# JACart.net
KiCad netlist of a schematic drawn in EAGLE
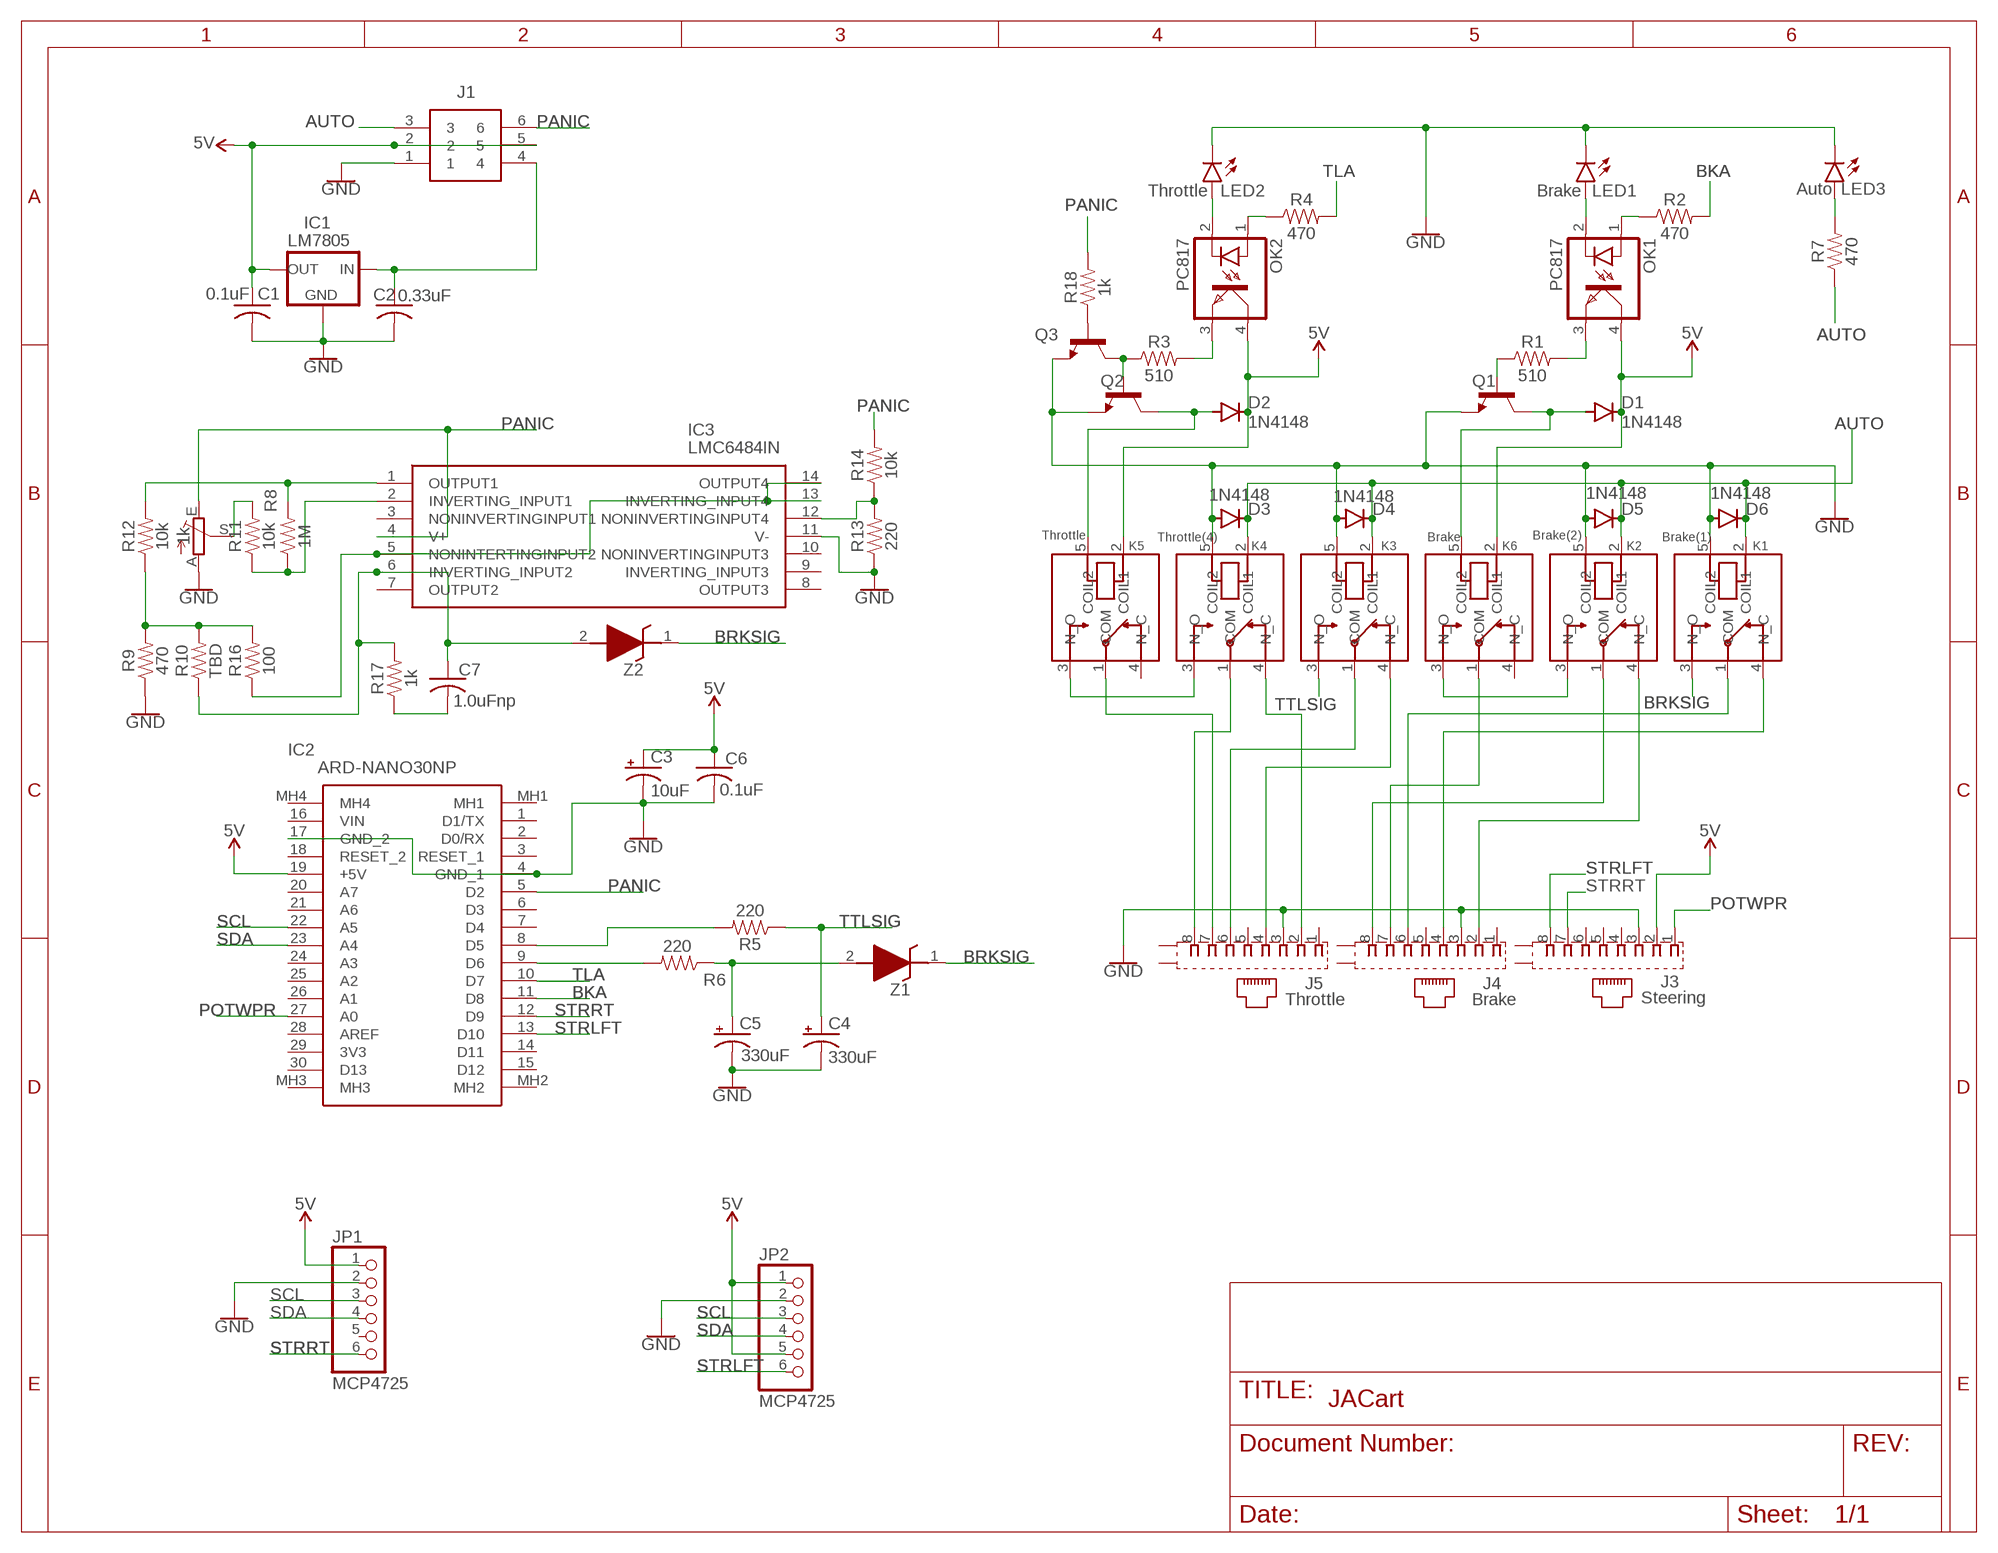
[diagram p0: schematic, sheet 1]

(export (version "E")
  (design (tool "Eeschema 10.0.6"))
  (components
    (comp (ref "C1")
      (value "0.1uF")
      (footprint "eagle-import:C050-024X044")
      (fields (field (name "C1") "0.1uF"))
      (libsource (lib "eagle-import") (part "adafruit_C-US050-024X044"))
    )
    (comp (ref "C2")
      (value "0.33uF")
      (footprint "eagle-import:C050-024X044")
      (fields (field (name "C2") "0.33uF"))
      (libsource (lib "eagle-import") (part "adafruit_C-US050-024X044"))
    )
    (comp (ref "C3")
      (value "10uF")
      (footprint "eagle-import:CPOL-RADIAL-2.5MM-5MM")
      (libsource (lib "eagle-import") (part "10UF-POLAR-RADIAL-2.5MM-25V-20%"))
    )
    (comp (ref "C4")
      (value "330uF")
      (footprint "eagle-import:PANASONIC_A")
      (libsource (lib "eagle-import") (part "330UF-PA"))
    )
    (comp (ref "C5")
      (value "330uF")
      (footprint "eagle-import:PANASONIC_A")
      (libsource (lib "eagle-import") (part "330UF-PA"))
    )
    (comp (ref "C6")
      (value "0.1uF")
      (footprint "eagle-import:C050-024X044")
      (fields (field (name "C6") "0.1uF"))
      (libsource (lib "eagle-import") (part "adafruit_C-US050-024X044"))
    )
    (comp (ref "C7")
      (value "1.0uF")
      (footprint "eagle-import:C050-024X044")
      (fields (field (name "C7") "1.0uFnp"))
      (libsource (lib "eagle-import") (part "C-US050-024X044"))
    )
    (comp (ref "D1")
      (value "1N4148")
      (footprint "eagle-import:DO35-7")
      (libsource (lib "eagle-import") (part "1N4148DO35-7"))
    )
    (comp (ref "D2")
      (value "1N4148")
      (footprint "eagle-import:DO35-7")
      (libsource (lib "eagle-import") (part "1N4148DO35-7"))
    )
    (comp (ref "D3")
      (value "1N4148")
      (footprint "eagle-import:DO35-7")
      (libsource (lib "eagle-import") (part "1N4148DO35-7"))
    )
    (comp (ref "D4")
      (value "1N4148")
      (footprint "eagle-import:DO35-7")
      (libsource (lib "eagle-import") (part "1N4148DO35-7"))
    )
    (comp (ref "D5")
      (value "1N4148")
      (footprint "eagle-import:DO35-7")
      (libsource (lib "eagle-import") (part "1N4148DO35-7"))
    )
    (comp (ref "D6")
      (value "1N4148")
      (footprint "eagle-import:DO35-7")
      (libsource (lib "eagle-import") (part "1N4148DO35-7"))
    )
    (comp (ref "IC1")
      (value "LM7805")
      (footprint "eagle-import:78XXS")
      (libsource (lib "eagle-import") (part "7805-VR"))
    )
    (comp (ref "IC2")
      (value "ARD-NANO30NP")
      (footprint "eagle-import:ARDNANO30NP")
      (fields (field (name "MOUSER_PART_NUMBER") "992-ARD-NANO30NP"))
      (libsource (lib "eagle-import") (part "ARD-NANO30NP"))
    )
    (comp (ref "IC3")
      (value "LMC6484IN")
      (footprint "eagle-import:DIP794W56P254L1905H533Q14N")
      (fields (field (name "MOUSER_PART_NUMBER") "926-LMC6484IN"))
      (libsource (lib "eagle-import") (part "LMC6484IN"))
    )
    (comp (ref "J1")
      (value "39-30-1060")
      (footprint "eagle-import:39-30-1060_1")
      (fields (field (name "MOUSER_PART_NUMBER") "538-39-30-1060"))
      (libsource (lib "eagle-import") (part "39-30-1060"))
    )
    (comp (ref "J3")
      (value "Steering")
      (footprint "eagle-import:GLX-S-88M")
      (libsource (lib "eagle-import") (part "RJ45-RTANGL"))
    )
    (comp (ref "J4")
      (value "Brake")
      (footprint "eagle-import:GLX-S-88M")
      (fields (field (name "MF") "J4"))
      (libsource (lib "eagle-import") (part "RJ45-RTANGL"))
    )
    (comp (ref "J5")
      (value "Throttle")
      (footprint "eagle-import:GLX-S-88M")
      (libsource (lib "eagle-import") (part "RJ45-RTANGL"))
    )
    (comp (ref "JP1")
      (value "MCP4725")
      (footprint "eagle-import:1X06_ROUND_70")
      (libsource (lib "eagle-import") (part "HEADER-1X670MIL"))
    )
    (comp (ref "JP2")
      (value "MCP4725")
      (footprint "eagle-import:1X06_ROUND_70")
      (libsource (lib "eagle-import") (part "HEADER-1X670MIL"))
    )
    (comp (ref "K1")
      (value "Brake(1)")
      (footprint "eagle-import:RELAY_JS1-5V-F")
      (fields (field (name "MF") "Panasonic Electric") (field (name "MP") "JS1-5V-F"))
      (libsource (lib "eagle-import") (part "RELAY-SPDT"))
    )
    (comp (ref "K2")
      (value "Brake(2)")
      (footprint "eagle-import:RELAY_JS1-5V-F")
      (fields (field (name "MF") "Panasonic Electric") (field (name "MP") "JS1-5V-F"))
      (libsource (lib "eagle-import") (part "RELAY-SPDT"))
    )
    (comp (ref "K3")
      (value "Throttle(3)")
      (footprint "eagle-import:RELAY_JS1-5V-F")
      (fields (field (name "MF") "Panasonic Electric") (field (name "MP") "JS1-5V-F"))
      (libsource (lib "eagle-import") (part "RELAY-SPDT"))
    )
    (comp (ref "K4")
      (value "Throttle(4)")
      (footprint "eagle-import:RELAY_JS1-5V-F")
      (fields (field (name "MF") "Panasonic Electric") (field (name "MP") "JS1-5V-F"))
      (libsource (lib "eagle-import") (part "RELAY-SPDT"))
    )
    (comp (ref "K5")
      (value "Throttle")
      (footprint "eagle-import:RELAY_JS1-5V-F")
      (fields (field (name "MF") "Panasonic Electric") (field (name "MP") "JS1-5V-F"))
      (libsource (lib "eagle-import") (part "RELAY-SPDT"))
    )
    (comp (ref "K6")
      (value "Brake")
      (footprint "eagle-import:RELAY_JS1-5V-F")
      (fields (field (name "MF") "Panasonic Electric") (field (name "MP") "JS1-5V-F"))
      (libsource (lib "eagle-import") (part "RELAY-SPDT"))
    )
    (comp (ref "LED1")
      (value "Brake")
      (footprint "eagle-import:LED_5MM")
      (libsource (lib "eagle-import") (part "LED5MM"))
    )
    (comp (ref "LED2")
      (value "Throttle")
      (footprint "eagle-import:LED_5MM")
      (libsource (lib "eagle-import") (part "LED5MM"))
    )
    (comp (ref "LED3")
      (value "Auto")
      (footprint "eagle-import:LED_5MM")
      (libsource (lib "eagle-import") (part "LED5MM"))
    )
    (comp (ref "OK1")
      (value "PC817")
      (footprint "eagle-import:DIL04")
      (fields (field (name "MPN") "PC817X4J000F"))
      (libsource (lib "eagle-import") (part "PC817"))
    )
    (comp (ref "OK2")
      (value "PC817")
      (footprint "eagle-import:DIL04")
      (fields (field (name "MPN") "PC817X4J000F"))
      (libsource (lib "eagle-import") (part "PC817"))
    )
    (comp (ref "Q1")
      (value "2N3904")
      (footprint "eagle-import:TO92")
      (libsource (lib "eagle-import") (part "2N3904"))
    )
    (comp (ref "Q2")
      (value "2N3904")
      (footprint "eagle-import:TO92")
      (libsource (lib "eagle-import") (part "2N3904"))
    )
    (comp (ref "Q3")
      (value "2N3904")
      (footprint "eagle-import:TO92")
      (libsource (lib "eagle-import") (part "2N3904"))
    )
    (comp (ref "R1")
      (value "510")
      (footprint "eagle-import:AXIAL-0.3")
      (libsource (lib "eagle-import") (part "RESISTORAXIAL-0.3"))
    )
    (comp (ref "R2")
      (value "470")
      (footprint "eagle-import:AXIAL-0.3")
      (libsource (lib "eagle-import") (part "RESISTORAXIAL-0.3"))
    )
    (comp (ref "R3")
      (value "510")
      (footprint "eagle-import:AXIAL-0.3")
      (libsource (lib "eagle-import") (part "RESISTORAXIAL-0.3"))
    )
    (comp (ref "R4")
      (value "470")
      (footprint "eagle-import:AXIAL-0.3")
      (libsource (lib "eagle-import") (part "RESISTORAXIAL-0.3"))
    )
    (comp (ref "R5")
      (value "220")
      (footprint "eagle-import:AXIAL-0.3")
      (libsource (lib "eagle-import") (part "RESISTORAXIAL-0.3"))
    )
    (comp (ref "R6")
      (value "220")
      (footprint "eagle-import:AXIAL-0.3")
      (libsource (lib "eagle-import") (part "RESISTORAXIAL-0.3"))
    )
    (comp (ref "R7")
      (value "470")
      (footprint "eagle-import:AXIAL-0.3")
      (libsource (lib "eagle-import") (part "RESISTORAXIAL-0.3"))
    )
    (comp (ref "R8")
      (value "1M")
      (footprint "eagle-import:AXIAL-0.3")
      (libsource (lib "eagle-import") (part "RESISTORAXIAL-0.3"))
    )
    (comp (ref "R9")
      (value "470")
      (footprint "eagle-import:AXIAL-0.3")
      (libsource (lib "eagle-import") (part "RESISTORAXIAL-0.3"))
    )
    (comp (ref "R10")
      (value "TBD")
      (footprint "eagle-import:AXIAL-0.3")
      (libsource (lib "eagle-import") (part "RESISTORAXIAL-0.3"))
    )
    (comp (ref "R11")
      (value "10k")
      (footprint "eagle-import:AXIAL-0.3")
      (libsource (lib "eagle-import") (part "RESISTORAXIAL-0.3"))
    )
    (comp (ref "R12")
      (value "10k")
      (footprint "eagle-import:AXIAL-0.3")
      (libsource (lib "eagle-import") (part "RESISTORAXIAL-0.3"))
    )
    (comp (ref "R13")
      (value "220")
      (footprint "eagle-import:AXIAL-0.3")
      (libsource (lib "eagle-import") (part "RESISTORAXIAL-0.3"))
    )
    (comp (ref "R14")
      (value "10k")
      (footprint "eagle-import:AXIAL-0.3")
      (libsource (lib "eagle-import") (part "RESISTORAXIAL-0.3"))
    )
    (comp (ref "R15")
      (value "1k")
      (footprint "eagle-import:RJ9W")
      (libsource (lib "eagle-import") (part "TRIM_EU-RJ9W"))
    )
    (comp (ref "R16")
      (value "100")
      (footprint "eagle-import:AXIAL-0.3")
      (libsource (lib "eagle-import") (part "RESISTORAXIAL-0.3"))
    )
    (comp (ref "R17")
      (value "1k")
      (footprint "eagle-import:AXIAL-0.3")
      (libsource (lib "eagle-import") (part "RESISTORAXIAL-0.3"))
    )
    (comp (ref "R18")
      (value "1k")
      (footprint "eagle-import:AXIAL-0.3")
      (libsource (lib "eagle-import") (part "RESISTORAXIAL-0.3"))
    )
    (comp (ref "Z1")
      (value "BAT85S-TR")
      (footprint "eagle-import:DIOAD950W60L350D150")
      (fields (field (name "MOUSER_PART_NUMBER") "78-BAT85S"))
      (libsource (lib "eagle-import") (part "BAT85S-TR"))
    )
    (comp (ref "Z2")
      (value "BAT85S-TR")
      (footprint "eagle-import:DIOAD950W60L350D150")
      (fields (field (name "MOUSER_PART_NUMBER") "78-BAT85S"))
      (libsource (lib "eagle-import") (part "BAT85S-TR"))
    )
  )
  (nets
    (net (code "1") (name "/AUTO") (class "Default")
      (node (ref "D3") (pin "C") (pinfunction "C_C") (pintype "passive"))
      (node (ref "D4") (pin "C") (pinfunction "C_C") (pintype "passive"))
      (node (ref "D5") (pin "C") (pinfunction "C_C") (pintype "passive"))
      (node (ref "D6") (pin "C") (pinfunction "C_C") (pintype "passive"))
      (node (ref "J1") (pin "3") (pinfunction "3_3") (pintype "bidirectional"))
      (node (ref "K1") (pin "2") (pinfunction "COIL1_2") (pintype "passive"))
      (node (ref "K2") (pin "2") (pinfunction "COIL1_2") (pintype "passive"))
      (node (ref "K3") (pin "2") (pinfunction "COIL1_2") (pintype "passive"))
      (node (ref "K4") (pin "2") (pinfunction "COIL1_2") (pintype "passive"))
      (node (ref "R7") (pin "P$1") (pinfunction "1_P$1") (pintype "passive"))
    )
    (net (code "2") (name "/BKA") (class "Default")
      (node (ref "IC2") (pin "11") (pinfunction "D8_11") (pintype "bidirectional"))
      (node (ref "R2") (pin "P$2") (pinfunction "2_P$2") (pintype "passive"))
    )
    (net (code "3") (name "/BRKSIG") (class "Default")
      (node (ref "K1") (pin "3") (pinfunction "N_O_3") (pintype "passive"))
      (node (ref "Z1") (pin "1") (pinfunction "K_1") (pintype "bidirectional"))
      (node (ref "Z2") (pin "1") (pinfunction "K_1") (pintype "bidirectional"))
    )
    (net (code "4") (name "/PANIC") (class "Default")
      (node (ref "IC2") (pin "5") (pinfunction "D2_5") (pintype "bidirectional"))
      (node (ref "IC3") (pin "4") (pinfunction "V+_4") (pintype "bidirectional"))
      (node (ref "J1") (pin "6") (pinfunction "6_6") (pintype "bidirectional"))
      (node (ref "R14") (pin "P$2") (pinfunction "2_P$2") (pintype "passive"))
      (node (ref "R15") (pin "E") (pinfunction "E_E") (pintype "passive"))
      (node (ref "R18") (pin "P$2") (pinfunction "2_P$2") (pintype "passive"))
    )
    (net (code "5") (name "/POTWPR") (class "Default")
      (node (ref "IC2") (pin "27") (pinfunction "A0_27") (pintype "bidirectional"))
      (node (ref "J3") (pin "1") (pinfunction "1_1") (pintype "passive"))
    )
    (net (code "6") (name "/SCL") (class "Default")
      (node (ref "IC2") (pin "22") (pinfunction "A5_22") (pintype "bidirectional"))
      (node (ref "JP1") (pin "3") (pinfunction "3_3") (pintype "passive"))
      (node (ref "JP2") (pin "3") (pinfunction "3_3") (pintype "passive"))
    )
    (net (code "7") (name "/SDA") (class "Default")
      (node (ref "IC2") (pin "23") (pinfunction "A4_23") (pintype "bidirectional"))
      (node (ref "JP1") (pin "4") (pinfunction "4_4") (pintype "passive"))
      (node (ref "JP2") (pin "4") (pinfunction "4_4") (pintype "passive"))
    )
    (net (code "8") (name "/STRLFT") (class "Default")
      (node (ref "IC2") (pin "13") (pinfunction "D10_13") (pintype "bidirectional"))
      (node (ref "J3") (pin "8") (pinfunction "8_8") (pintype "passive"))
      (node (ref "JP2") (pin "6") (pinfunction "6_6") (pintype "passive"))
    )
    (net (code "9") (name "/STRRT") (class "Default")
      (node (ref "IC2") (pin "12") (pinfunction "D9_12") (pintype "bidirectional"))
      (node (ref "J3") (pin "7") (pinfunction "7_7") (pintype "passive"))
      (node (ref "JP1") (pin "6") (pinfunction "6_6") (pintype "passive"))
    )
    (net (code "10") (name "/TLA") (class "Default")
      (node (ref "IC2") (pin "10") (pinfunction "D7_10") (pintype "bidirectional"))
      (node (ref "R4") (pin "P$2") (pinfunction "2_P$2") (pintype "passive"))
    )
    (net (code "11") (name "/TTLSIG") (class "Default")
      (node (ref "C4") (pin "+") (pinfunction "+_+") (pintype "passive"))
      (node (ref "K3") (pin "3") (pinfunction "N_O_3") (pintype "passive"))
      (node (ref "R5") (pin "P$1") (pinfunction "1_P$1") (pintype "passive"))
    )
    (net (code "12") (name "5V") (class "Default")
      (node (ref "C1") (pin "1") (pinfunction "1_1") (pintype "passive"))
      (node (ref "C3") (pin "1") (pinfunction "+_1") (pintype "passive"))
      (node (ref "C6") (pin "1") (pinfunction "1_1") (pintype "passive"))
      (node (ref "D1") (pin "C") (pinfunction "C_C") (pintype "passive"))
      (node (ref "D2") (pin "C") (pinfunction "C_C") (pintype "passive"))
      (node (ref "IC1") (pin "OUT") (pinfunction "OUT_OUT") (pintype "passive"))
      (node (ref "IC2") (pin "19") (pinfunction "+5V_19") (pintype "bidirectional"))
      (node (ref "J1") (pin "2") (pinfunction "2_2") (pintype "bidirectional"))
      (node (ref "J1") (pin "5") (pinfunction "5_5") (pintype "bidirectional"))
      (node (ref "J3") (pin "2") (pinfunction "2_2") (pintype "passive"))
      (node (ref "JP1") (pin "1") (pinfunction "1_1") (pintype "passive"))
      (node (ref "JP2") (pin "1") (pinfunction "1_1") (pintype "passive"))
      (node (ref "JP2") (pin "5") (pinfunction "5_5") (pintype "passive"))
      (node (ref "K5") (pin "2") (pinfunction "COIL1_2") (pintype "passive"))
      (node (ref "K6") (pin "2") (pinfunction "COIL1_2") (pintype "passive"))
      (node (ref "OK1") (pin "4") (pinfunction "COL_4") (pintype "passive"))
      (node (ref "OK2") (pin "4") (pinfunction "COL_4") (pintype "passive"))
    )
    (net (code "13") (name "GND") (class "Default")
      (node (ref "C1") (pin "2") (pinfunction "2_2") (pintype "passive"))
      (node (ref "C2") (pin "2") (pinfunction "2_2") (pintype "passive"))
      (node (ref "C3") (pin "2") (pinfunction "-_2") (pintype "passive"))
      (node (ref "C4") (pin "-") (pinfunction "-_-") (pintype "passive"))
      (node (ref "C5") (pin "-") (pinfunction "-_-") (pintype "passive"))
      (node (ref "C6") (pin "2") (pinfunction "2_2") (pintype "passive"))
      (node (ref "D3") (pin "A") (pinfunction "A_A") (pintype "passive"))
      (node (ref "D4") (pin "A") (pinfunction "A_A") (pintype "passive"))
      (node (ref "D5") (pin "A") (pinfunction "A_A") (pintype "passive"))
      (node (ref "D6") (pin "A") (pinfunction "A_A") (pintype "passive"))
      (node (ref "IC1") (pin "GND") (pinfunction "GND_GND") (pintype "input"))
      (node (ref "IC2") (pin "17") (pinfunction "GND_2_17") (pintype "bidirectional"))
      (node (ref "IC2") (pin "4") (pinfunction "GND_1_4") (pintype "bidirectional"))
      (node (ref "IC3") (pin "11") (pinfunction "V-_11") (pintype "bidirectional"))
      (node (ref "J1") (pin "1") (pinfunction "1_1") (pintype "bidirectional"))
      (node (ref "J3") (pin "3") (pinfunction "3_3") (pintype "passive"))
      (node (ref "J4") (pin "3") (pinfunction "3_3") (pintype "passive"))
      (node (ref "J5") (pin "3") (pinfunction "3_3") (pintype "passive"))
      (node (ref "JP1") (pin "2") (pinfunction "2_2") (pintype "passive"))
      (node (ref "JP2") (pin "2") (pinfunction "2_2") (pintype "passive"))
      (node (ref "K1") (pin "5") (pinfunction "COIL2_5") (pintype "passive"))
      (node (ref "K2") (pin "5") (pinfunction "COIL2_5") (pintype "passive"))
      (node (ref "K3") (pin "5") (pinfunction "COIL2_5") (pintype "passive"))
      (node (ref "K4") (pin "5") (pinfunction "COIL2_5") (pintype "passive"))
      (node (ref "LED1") (pin "K") (pinfunction "C_K") (pintype "passive"))
      (node (ref "LED2") (pin "K") (pinfunction "C_K") (pintype "passive"))
      (node (ref "LED3") (pin "K") (pinfunction "C_K") (pintype "passive"))
      (node (ref "Q1") (pin "3") (pinfunction "E_3") (pintype "passive"))
      (node (ref "Q2") (pin "3") (pinfunction "E_3") (pintype "passive"))
      (node (ref "Q3") (pin "3") (pinfunction "E_3") (pintype "passive"))
      (node (ref "R13") (pin "P$1") (pinfunction "1_P$1") (pintype "passive"))
      (node (ref "R15") (pin "A") (pinfunction "A_A") (pintype "passive"))
      (node (ref "R9") (pin "P$1") (pinfunction "1_P$1") (pintype "passive"))
    )
    (net (code "14") (name "Net-(C2-Pad1)") (class "Default")
      (node (ref "C2") (pin "1") (pinfunction "1_1") (pintype "passive"))
      (node (ref "IC1") (pin "IN") (pinfunction "IN_IN") (pintype "input"))
      (node (ref "J1") (pin "4") (pinfunction "4_4") (pintype "bidirectional"))
    )
    (net (code "15") (name "Net-(IC2-D5)") (class "Default")
      (node (ref "IC2") (pin "8") (pinfunction "D5_8") (pintype "bidirectional"))
      (node (ref "R5") (pin "P$2") (pinfunction "2_P$2") (pintype "passive"))
    )
    (net (code "16") (name "Net-(IC2-D6)") (class "Default")
      (node (ref "IC2") (pin "9") (pinfunction "D6_9") (pintype "bidirectional"))
      (node (ref "R6") (pin "P$2") (pinfunction "2_P$2") (pintype "passive"))
    )
    (net (code "17") (name "Net-(IC3-INVERTING_INPUT1)") (class "Default")
      (node (ref "IC3") (pin "2") (pinfunction "INVERTING_INPUT1_2") (pintype "bidirectional"))
      (node (ref "R11") (pin "P$1") (pinfunction "1_P$1") (pintype "passive"))
      (node (ref "R8") (pin "P$1") (pinfunction "1_P$1") (pintype "passive"))
    )
    (net (code "18") (name "Net-(IC3-INVERTING_INPUT2)") (class "Default")
      (node (ref "C7") (pin "1") (pinfunction "1_1") (pintype "passive"))
      (node (ref "IC3") (pin "6") (pinfunction "INVERTING_INPUT2_6") (pintype "bidirectional"))
      (node (ref "R10") (pin "P$1") (pinfunction "1_P$1") (pintype "passive"))
      (node (ref "R17") (pin "P$2") (pinfunction "2_P$2") (pintype "passive"))
      (node (ref "Z2") (pin "2") (pinfunction "A_2") (pintype "bidirectional"))
    )
    (net (code "19") (name "Net-(IC3-INVERTING_INPUT4)") (class "Default")
      (node (ref "IC3") (pin "13") (pinfunction "INVERTING_INPUT4_13") (pintype "bidirectional"))
      (node (ref "IC3") (pin "14") (pinfunction "OUTPUT4_14") (pintype "bidirectional"))
      (node (ref "IC3") (pin "5") (pinfunction "NONINTERTINGINPUT2_5") (pintype "bidirectional"))
      (node (ref "R16") (pin "P$1") (pinfunction "1_P$1") (pintype "passive"))
    )
    (net (code "20") (name "Net-(IC3-NONINVERTINGINPUT4)") (class "Default")
      (node (ref "IC3") (pin "12") (pinfunction "NONINVERTINGINPUT4_12") (pintype "bidirectional"))
      (node (ref "R13") (pin "P$2") (pinfunction "2_P$2") (pintype "passive"))
      (node (ref "R14") (pin "P$1") (pinfunction "1_P$1") (pintype "passive"))
    )
    (net (code "21") (name "Net-(IC3-OUTPUT1)") (class "Default")
      (node (ref "IC3") (pin "1") (pinfunction "OUTPUT1_1") (pintype "bidirectional"))
      (node (ref "R12") (pin "P$2") (pinfunction "2_P$2") (pintype "passive"))
      (node (ref "R8") (pin "P$2") (pinfunction "2_P$2") (pintype "passive"))
    )
    (net (code "22") (name "Net-(K1-COM)") (class "Default")
      (node (ref "J4") (pin "6") (pinfunction "6_6") (pintype "passive"))
      (node (ref "K1") (pin "1") (pinfunction "COM_1") (pintype "passive"))
    )
    (net (code "23") (name "Net-(K1-N_C)") (class "Default")
      (node (ref "J4") (pin "4") (pinfunction "4_4") (pintype "passive"))
      (node (ref "K1") (pin "4") (pinfunction "N_C_4") (pintype "passive"))
    )
    (net (code "24") (name "Net-(K2-COM)") (class "Default")
      (node (ref "J4") (pin "8") (pinfunction "8_8") (pintype "passive"))
      (node (ref "K2") (pin "1") (pinfunction "COM_1") (pintype "passive"))
    )
    (net (code "25") (name "Net-(K2-N_C)") (class "Default")
      (node (ref "J4") (pin "2") (pinfunction "2_2") (pintype "passive"))
      (node (ref "K2") (pin "4") (pinfunction "N_C_4") (pintype "passive"))
    )
    (net (code "26") (name "Net-(K2-N_O)") (class "Default")
      (node (ref "K2") (pin "3") (pinfunction "N_O_3") (pintype "passive"))
      (node (ref "K6") (pin "3") (pinfunction "N_O_3") (pintype "passive"))
    )
    (net (code "27") (name "Net-(K3-COM)") (class "Default")
      (node (ref "J5") (pin "6") (pinfunction "6_6") (pintype "passive"))
      (node (ref "K3") (pin "1") (pinfunction "COM_1") (pintype "passive"))
    )
    (net (code "28") (name "Net-(K3-N_C)") (class "Default")
      (node (ref "J5") (pin "4") (pinfunction "4_4") (pintype "passive"))
      (node (ref "K3") (pin "4") (pinfunction "N_C_4") (pintype "passive"))
    )
    (net (code "29") (name "Net-(K4-COM)") (class "Default")
      (node (ref "J5") (pin "8") (pinfunction "8_8") (pintype "passive"))
      (node (ref "K4") (pin "1") (pinfunction "COM_1") (pintype "passive"))
    )
    (net (code "30") (name "Net-(K4-N_C)") (class "Default")
      (node (ref "J5") (pin "2") (pinfunction "2_2") (pintype "passive"))
      (node (ref "K4") (pin "4") (pinfunction "N_C_4") (pintype "passive"))
    )
    (net (code "31") (name "Net-(K4-N_O)") (class "Default")
      (node (ref "K4") (pin "3") (pinfunction "N_O_3") (pintype "passive"))
      (node (ref "K5") (pin "3") (pinfunction "N_O_3") (pintype "passive"))
    )
    (net (code "32") (name "Net-(K5-COIL2)") (class "Default")
      (node (ref "D2") (pin "A") (pinfunction "A_A") (pintype "passive"))
      (node (ref "K5") (pin "5") (pinfunction "COIL2_5") (pintype "passive"))
      (node (ref "Q2") (pin "1") (pinfunction "C_1") (pintype "passive"))
    )
    (net (code "33") (name "Net-(K5-COM)") (class "Default")
      (node (ref "J5") (pin "7") (pinfunction "7_7") (pintype "passive"))
      (node (ref "K5") (pin "1") (pinfunction "COM_1") (pintype "passive"))
    )
    (net (code "34") (name "Net-(K6-COIL2)") (class "Default")
      (node (ref "D1") (pin "A") (pinfunction "A_A") (pintype "passive"))
      (node (ref "K6") (pin "5") (pinfunction "COIL2_5") (pintype "passive"))
      (node (ref "Q1") (pin "1") (pinfunction "C_1") (pintype "passive"))
    )
    (net (code "35") (name "Net-(K6-COM)") (class "Default")
      (node (ref "J4") (pin "7") (pinfunction "7_7") (pintype "passive"))
      (node (ref "K6") (pin "1") (pinfunction "COM_1") (pintype "passive"))
    )
    (net (code "36") (name "Net-(OK1-A)") (class "Default")
      (node (ref "OK1") (pin "1") (pinfunction "A_1") (pintype "passive"))
      (node (ref "R2") (pin "P$1") (pinfunction "1_P$1") (pintype "passive"))
    )
    (net (code "37") (name "Net-(OK1-C)") (class "Default")
      (node (ref "LED1") (pin "A") (pinfunction "A_A") (pintype "passive"))
      (node (ref "OK1") (pin "2") (pinfunction "C_2") (pintype "passive"))
    )
    (net (code "38") (name "Net-(OK1-EMIT)") (class "Default")
      (node (ref "OK1") (pin "3") (pinfunction "EMIT_3") (pintype "passive"))
      (node (ref "R1") (pin "P$2") (pinfunction "2_P$2") (pintype "passive"))
    )
    (net (code "39") (name "Net-(OK2-A)") (class "Default")
      (node (ref "OK2") (pin "1") (pinfunction "A_1") (pintype "passive"))
      (node (ref "R4") (pin "P$1") (pinfunction "1_P$1") (pintype "passive"))
    )
    (net (code "40") (name "Net-(OK2-C)") (class "Default")
      (node (ref "LED2") (pin "A") (pinfunction "A_A") (pintype "passive"))
      (node (ref "OK2") (pin "2") (pinfunction "C_2") (pintype "passive"))
    )
    (net (code "41") (name "Net-(OK2-EMIT)") (class "Default")
      (node (ref "OK2") (pin "3") (pinfunction "EMIT_3") (pintype "passive"))
      (node (ref "R3") (pin "P$2") (pinfunction "2_P$2") (pintype "passive"))
    )
    (net (code "42") (name "Net-(Q1-B)") (class "Default")
      (node (ref "Q1") (pin "2") (pinfunction "B_2") (pintype "passive"))
      (node (ref "R1") (pin "P$1") (pinfunction "1_P$1") (pintype "passive"))
    )
    (net (code "43") (name "Net-(Q2-B)") (class "Default")
      (node (ref "Q2") (pin "2") (pinfunction "B_2") (pintype "passive"))
      (node (ref "Q3") (pin "1") (pinfunction "C_1") (pintype "passive"))
      (node (ref "R3") (pin "P$1") (pinfunction "1_P$1") (pintype "passive"))
    )
    (net (code "44") (name "Net-(Q3-B)") (class "Default")
      (node (ref "Q3") (pin "2") (pinfunction "B_2") (pintype "passive"))
      (node (ref "R18") (pin "P$1") (pinfunction "1_P$1") (pintype "passive"))
    )
    (net (code "45") (name "Net-(R6-1)") (class "Default")
      (node (ref "C5") (pin "+") (pinfunction "+_+") (pintype "passive"))
      (node (ref "R6") (pin "P$1") (pinfunction "1_P$1") (pintype "passive"))
      (node (ref "Z1") (pin "2") (pinfunction "A_2") (pintype "bidirectional"))
    )
    (net (code "46") (name "Net-(R7-2)") (class "Default")
      (node (ref "LED3") (pin "A") (pinfunction "A_A") (pintype "passive"))
      (node (ref "R7") (pin "P$2") (pinfunction "2_P$2") (pintype "passive"))
    )
    (net (code "47") (name "Net-(R10-2)") (class "Default")
      (node (ref "R10") (pin "P$2") (pinfunction "2_P$2") (pintype "passive"))
      (node (ref "R12") (pin "P$1") (pinfunction "1_P$1") (pintype "passive"))
      (node (ref "R16") (pin "P$2") (pinfunction "2_P$2") (pintype "passive"))
      (node (ref "R9") (pin "P$2") (pinfunction "2_P$2") (pintype "passive"))
    )
    (net (code "48") (name "Net-(R11-2)") (class "Default")
      (node (ref "R11") (pin "P$2") (pinfunction "2_P$2") (pintype "passive"))
      (node (ref "R15") (pin "S") (pinfunction "S_S") (pintype "passive"))
    )
    (net (code "49") (name "Net-(R17-1)") (class "Default")
      (node (ref "C7") (pin "2") (pinfunction "2_2") (pintype "passive"))
      (node (ref "R17") (pin "P$1") (pinfunction "1_P$1") (pintype "passive"))
    )
    (net (code "50") (name "unconnected-(IC2-3V3-Pad29)") (class "Default")
      (node (ref "IC2") (pin "29") (pinfunction "3V3_29") (pintype "bidirectional"))
    )
    (net (code "51") (name "unconnected-(IC2-A1-Pad26)") (class "Default")
      (node (ref "IC2") (pin "26") (pinfunction "A1_26") (pintype "bidirectional"))
    )
    (net (code "52") (name "unconnected-(IC2-A2-Pad25)") (class "Default")
      (node (ref "IC2") (pin "25") (pinfunction "A2_25") (pintype "bidirectional"))
    )
    (net (code "53") (name "unconnected-(IC2-A3-Pad24)") (class "Default")
      (node (ref "IC2") (pin "24") (pinfunction "A3_24") (pintype "bidirectional"))
    )
    (net (code "54") (name "unconnected-(IC2-A6-Pad21)") (class "Default")
      (node (ref "IC2") (pin "21") (pinfunction "A6_21") (pintype "bidirectional"))
    )
    (net (code "55") (name "unconnected-(IC2-A7-Pad20)") (class "Default")
      (node (ref "IC2") (pin "20") (pinfunction "A7_20") (pintype "bidirectional"))
    )
    (net (code "56") (name "unconnected-(IC2-AREF-Pad28)") (class "Default")
      (node (ref "IC2") (pin "28") (pinfunction "AREF_28") (pintype "bidirectional"))
    )
    (net (code "57") (name "unconnected-(IC2-D0{slash}RX-Pad2)") (class "Default")
      (node (ref "IC2") (pin "2") (pinfunction "D0/RX_2") (pintype "bidirectional"))
    )
    (net (code "58") (name "unconnected-(IC2-D1{slash}TX-Pad1)") (class "Default")
      (node (ref "IC2") (pin "1") (pinfunction "D1/TX_1") (pintype "bidirectional"))
    )
    (net (code "59") (name "unconnected-(IC2-D3-Pad6)") (class "Default")
      (node (ref "IC2") (pin "6") (pinfunction "D3_6") (pintype "bidirectional"))
    )
    (net (code "60") (name "unconnected-(IC2-D4-Pad7)") (class "Default")
      (node (ref "IC2") (pin "7") (pinfunction "D4_7") (pintype "bidirectional"))
    )
    (net (code "61") (name "unconnected-(IC2-D11-Pad14)") (class "Default")
      (node (ref "IC2") (pin "14") (pinfunction "D11_14") (pintype "bidirectional"))
    )
    (net (code "62") (name "unconnected-(IC2-D12-Pad15)") (class "Default")
      (node (ref "IC2") (pin "15") (pinfunction "D12_15") (pintype "bidirectional"))
    )
    (net (code "63") (name "unconnected-(IC2-D13-Pad30)") (class "Default")
      (node (ref "IC2") (pin "30") (pinfunction "D13_30") (pintype "bidirectional"))
    )
    (net (code "64") (name "unconnected-(IC2-PadMH1)") (class "Default")
      (node (ref "IC2") (pin "MH1") (pinfunction "MH1_MH1") (pintype "bidirectional"))
    )
    (net (code "65") (name "unconnected-(IC2-PadMH2)") (class "Default")
      (node (ref "IC2") (pin "MH2") (pinfunction "MH2_MH2") (pintype "bidirectional"))
    )
    (net (code "66") (name "unconnected-(IC2-PadMH3)") (class "Default")
      (node (ref "IC2") (pin "MH3") (pinfunction "MH3_MH3") (pintype "bidirectional"))
    )
    (net (code "67") (name "unconnected-(IC2-PadMH4)") (class "Default")
      (node (ref "IC2") (pin "MH4") (pinfunction "MH4_MH4") (pintype "bidirectional"))
    )
    (net (code "68") (name "unconnected-(IC2-RESET_1-Pad3)") (class "Default")
      (node (ref "IC2") (pin "3") (pinfunction "RESET_1_3") (pintype "bidirectional"))
    )
    (net (code "69") (name "unconnected-(IC2-RESET_2-Pad18)") (class "Default")
      (node (ref "IC2") (pin "18") (pinfunction "RESET_2_18") (pintype "bidirectional"))
    )
    (net (code "70") (name "unconnected-(IC2-VIN-Pad16)") (class "Default")
      (node (ref "IC2") (pin "16") (pinfunction "VIN_16") (pintype "bidirectional"))
    )
    (net (code "71") (name "unconnected-(IC3-INVERTING_INPUT3-Pad9)") (class "Default")
      (node (ref "IC3") (pin "9") (pinfunction "INVERTING_INPUT3_9") (pintype "bidirectional"))
    )
    (net (code "72") (name "unconnected-(IC3-NONINVERTINGINPUT1-Pad3)") (class "Default")
      (node (ref "IC3") (pin "3") (pinfunction "NONINVERTINGINPUT1_3") (pintype "bidirectional"))
    )
    (net (code "73") (name "unconnected-(IC3-NONINVERTINGINPUT3-Pad10)") (class "Default")
      (node (ref "IC3") (pin "10") (pinfunction "NONINVERTINGINPUT3_10") (pintype "bidirectional"))
    )
    (net (code "74") (name "unconnected-(IC3-OUTPUT2-Pad7)") (class "Default")
      (node (ref "IC3") (pin "7") (pinfunction "OUTPUT2_7") (pintype "bidirectional"))
    )
    (net (code "75") (name "unconnected-(IC3-OUTPUT3-Pad8)") (class "Default")
      (node (ref "IC3") (pin "8") (pinfunction "OUTPUT3_8") (pintype "bidirectional"))
    )
    (net (code "76") (name "unconnected-(J3-Pad4)") (class "Default")
      (node (ref "J3") (pin "4") (pinfunction "4_4") (pintype "passive"))
    )
    (net (code "77") (name "unconnected-(J3-Pad5)") (class "Default")
      (node (ref "J3") (pin "5") (pinfunction "5_5") (pintype "passive"))
    )
    (net (code "78") (name "unconnected-(J3-Pad6)") (class "Default")
      (node (ref "J3") (pin "6") (pinfunction "6_6") (pintype "passive"))
    )
    (net (code "79") (name "unconnected-(J3-PadS1)") (class "Default")
      (node (ref "J3") (pin "S1") (pinfunction "S1_S1") (pintype "passive"))
    )
    (net (code "80") (name "unconnected-(J3-PadS2)") (class "Default")
      (node (ref "J3") (pin "S2") (pinfunction "S2_S2") (pintype "passive"))
    )
    (net (code "81") (name "unconnected-(J4-Pad1)") (class "Default")
      (node (ref "J4") (pin "1") (pinfunction "1_1") (pintype "passive"))
    )
    (net (code "82") (name "unconnected-(J4-Pad5)") (class "Default")
      (node (ref "J4") (pin "5") (pinfunction "5_5") (pintype "passive"))
    )
    (net (code "83") (name "unconnected-(J4-PadS1)") (class "Default")
      (node (ref "J4") (pin "S1") (pinfunction "S1_S1") (pintype "passive"))
    )
    (net (code "84") (name "unconnected-(J4-PadS2)") (class "Default")
      (node (ref "J4") (pin "S2") (pinfunction "S2_S2") (pintype "passive"))
    )
    (net (code "85") (name "unconnected-(J5-Pad1)") (class "Default")
      (node (ref "J5") (pin "1") (pinfunction "1_1") (pintype "passive"))
    )
    (net (code "86") (name "unconnected-(J5-Pad5)") (class "Default")
      (node (ref "J5") (pin "5") (pinfunction "5_5") (pintype "passive"))
    )
    (net (code "87") (name "unconnected-(J5-PadS1)") (class "Default")
      (node (ref "J5") (pin "S1") (pinfunction "S1_S1") (pintype "passive"))
    )
    (net (code "88") (name "unconnected-(J5-PadS2)") (class "Default")
      (node (ref "J5") (pin "S2") (pinfunction "S2_S2") (pintype "passive"))
    )
    (net (code "89") (name "unconnected-(JP1-Pad5)") (class "Default")
      (node (ref "JP1") (pin "5") (pinfunction "5_5") (pintype "passive"))
    )
    (net (code "90") (name "unconnected-(K5-N_C-Pad4)") (class "Default")
      (node (ref "K5") (pin "4") (pinfunction "N_C_4") (pintype "passive"))
    )
    (net (code "91") (name "unconnected-(K6-N_C-Pad4)") (class "Default")
      (node (ref "K6") (pin "4") (pinfunction "N_C_4") (pintype "passive"))
    )
  )
)
